# SPDT_FET_SW_driver.net
KiCad netlist of a schematic drawn in Altium Designer
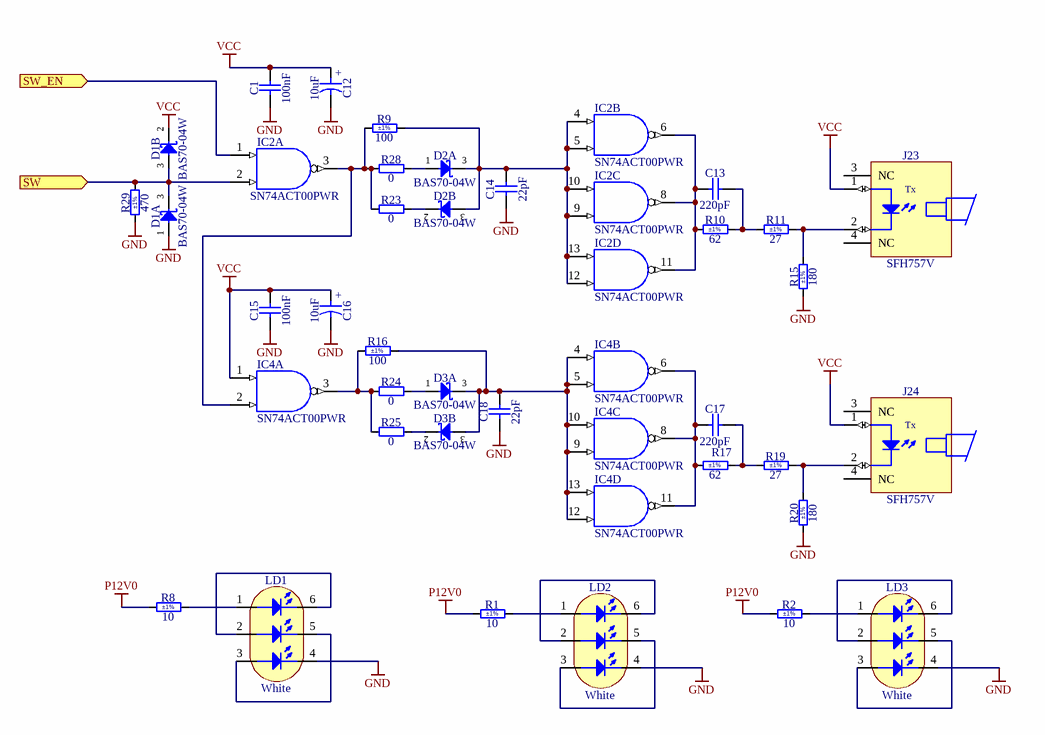
[diagram p0: SPDT_FET_SW_driver.SchDoc]

(export (version "E")
  (design (tool "Eeschema 10.0.6"))
  (components
    (comp (ref "C1")
      (value "100nF")
      (footprint "CAPC1005X55N")
      (description "Non-polarised capacitor")
      (fields
        (field (name "PART NUMBER") "CC0402_100NF_16V_10%_X7R")
        (field (name "VOLTAGE") "16V")
        (field (name "AUTHOR") "CERN DEM JLC")
      )
      (libsource (lib "Capacitors") (part "Capacitor - non polarized"))
    )
    (comp (ref "C12")
      (value "10uF")
      (footprint "CAPMP3216X180N")
      (description "Polarised capacitor")
      (fields
        (field (name "PART NUMBER") "CTE3216-18_10UF_16V_20%_AVX_TCJ")
        (field (name "VOLTAGE") "16V")
        (field (name "AUTHOR") "CERN DEM JLC")
      )
      (libsource (lib "Capacitors") (part "Capacitor - polarized"))
    )
    (comp (ref "C13")
      (value "220pF")
      (footprint "CAPC1608X87N")
      (description "Non-polarised capacitor")
      (fields
        (field (name "PART NUMBER") "CC0603_220PF_50V_5%_NP0")
        (field (name "VOLTAGE") "50V")
        (field (name "AUTHOR") "CERN DEM JLC")
      )
      (libsource (lib "Capacitors") (part "Capacitor - non polarized"))
    )
    (comp (ref "C14")
      (value "22pF")
      (footprint "CAPC1608X87N")
      (description "Non-polarised capacitor")
      (fields
        (field (name "PART NUMBER") "CC0603_22PF_50V_5%_NP0")
        (field (name "VOLTAGE") "50V")
        (field (name "AUTHOR") "CERN DEM JLC")
      )
      (libsource (lib "Capacitors") (part "Capacitor - non polarized"))
    )
    (comp (ref "C15")
      (value "100nF")
      (footprint "CAPC1005X55N")
      (description "Non-polarised capacitor")
      (fields
        (field (name "PART NUMBER") "CC0402_100NF_16V_10%_X7R")
        (field (name "VOLTAGE") "16V")
        (field (name "AUTHOR") "CERN DEM JLC")
      )
      (libsource (lib "Capacitors") (part "Capacitor - non polarized"))
    )
    (comp (ref "C16")
      (value "10uF")
      (footprint "CAPMP3216X180N")
      (description "Polarised capacitor")
      (fields
        (field (name "PART NUMBER") "CTE3216-18_10UF_16V_20%_AVX_TCJ")
        (field (name "VOLTAGE") "16V")
        (field (name "AUTHOR") "CERN DEM JLC")
      )
      (libsource (lib "Capacitors") (part "Capacitor - polarized"))
    )
    (comp (ref "C17")
      (value "220pF")
      (footprint "CAPC1608X87N")
      (description "Non-polarised capacitor")
      (fields
        (field (name "PART NUMBER") "CC0603_220PF_50V_5%_NP0")
        (field (name "VOLTAGE") "50V")
        (field (name "AUTHOR") "CERN DEM JLC")
      )
      (libsource (lib "Capacitors") (part "Capacitor - non polarized"))
    )
    (comp (ref "C18")
      (value "22pF")
      (footprint "CAPC1608X87N")
      (description "Non-polarised capacitor")
      (fields
        (field (name "PART NUMBER") "CC0603_22PF_50V_5%_NP0")
        (field (name "VOLTAGE") "50V")
        (field (name "AUTHOR") "CERN DEM JLC")
      )
      (libsource (lib "Capacitors") (part "Capacitor - non polarized"))
    )
    (comp (ref "D1")
      (value "BAS70-04W")
      (footprint "SOT65P210X110-3N")
      (description "Serial Schottky Diode")
      (fields
        (field (name "VOLTAGE") "70V")
        (field (name "POWER") "70mA")
        (field (name "AUTHOR") "CERN DEM JLC")
      )
      (libsource (lib "ICs And Semiconductors") (part "Diode Schottky x2 A1C3_A3C2"))
    )
    (comp (ref "D2")
      (value "BAS70-04W")
      (footprint "SOT65P210X110-3N")
      (description "Serial Schottky Diode")
      (fields
        (field (name "VOLTAGE") "70V")
        (field (name "POWER") "70mA")
        (field (name "AUTHOR") "CERN DEM JLC")
      )
      (libsource (lib "ICs And Semiconductors") (part "Diode Schottky x2 A1C3_A3C2"))
    )
    (comp (ref "D3")
      (value "BAS70-04W")
      (footprint "SOT65P210X110-3N")
      (description "Serial Schottky Diode")
      (fields
        (field (name "VOLTAGE") "70V")
        (field (name "POWER") "70mA")
        (field (name "AUTHOR") "CERN DEM JLC")
      )
      (libsource (lib "ICs And Semiconductors") (part "Diode Schottky x2 A1C3_A3C2"))
    )
    (comp (ref "IC2")
      (value "SN74ACT00PWR")
      (footprint "SOP65P640X120-14N")
      (description "Quad 2-Input NAND Gate")
      (fields (field (name "MANUFACTURER") "TEXAS INSTRUMENTS") (field (name "AUTHOR") "CERN DEM JLC"))
      (libsource (lib "ICs And Semiconductors") (part "7400"))
    )
    (comp (ref "IC4")
      (value "SN74ACT00PWR")
      (footprint "SOP65P640X120-14N")
      (description "Quad 2-Input NAND Gate")
      (fields (field (name "MANUFACTURER") "TEXAS INSTRUMENTS") (field (name "AUTHOR") "CERN DEM JLC"))
      (libsource (lib "ICs And Semiconductors") (part "7400"))
    )
    (comp (ref "J23")
      (value "SFH757V")
      (footprint "SFH756V")
      (description "Plastic Connector Housing For Plastic Fiber Optic Photodiode Detector")
      (fields
        (field (name "MANUFACTURER") "AVAGO TECHNOLOGIES")
        (field (name "MANUFACTURER PART NUMBER") "SFH756V or SP000063814")
        (field (name "AUTHOR") "CERN DEM JLC")
      )
      (libsource (lib "Connectors") (part "SFH756V"))
    )
    (comp (ref "J24")
      (value "SFH757V")
      (footprint "SFH756V")
      (description "Plastic Connector Housing For Plastic Fiber Optic Photodiode Detector")
      (fields
        (field (name "MANUFACTURER") "AVAGO TECHNOLOGIES")
        (field (name "MANUFACTURER PART NUMBER") "SFH756V or SP000063814")
        (field (name "AUTHOR") "CERN DEM JLC")
      )
      (libsource (lib "Connectors") (part "SFH756V"))
    )
    (comp (ref "LD1")
      (value "White")
      (footprint "LED_CREE_CLP6B-WKW")
      (description "PLCC6 3 in 1 Surface Mount, Cool White LED")
      (fields
        (field (name "PART NUMBER") "LED_CREE_CLP6B-WKW-CD0E0233")
        (field (name "MANUFACTURER") "CREE")
        (field (name "AUTHOR") "CERN DEM JMW")
      )
      (libsource (lib "ICs And Semiconductors") (part "LED_CREE_CLP6B-WKW"))
    )
    (comp (ref "LD2")
      (value "White")
      (footprint "LED_CREE_CLP6B-WKW")
      (description "PLCC6 3 in 1 Surface Mount, Cool White LED")
      (fields
        (field (name "PART NUMBER") "LED_CREE_CLP6B-WKW-CD0E0233")
        (field (name "MANUFACTURER") "CREE")
        (field (name "AUTHOR") "CERN DEM JMW")
      )
      (libsource (lib "ICs And Semiconductors") (part "LED_CREE_CLP6B-WKW"))
    )
    (comp (ref "LD3")
      (value "White")
      (footprint "LED_CREE_CLP6B-WKW")
      (description "PLCC6 3 in 1 Surface Mount, Cool White LED")
      (fields
        (field (name "PART NUMBER") "LED_CREE_CLP6B-WKW-CD0E0233")
        (field (name "MANUFACTURER") "CREE")
        (field (name "AUTHOR") "CERN DEM JMW")
      )
      (libsource (lib "ICs And Semiconductors") (part "LED_CREE_CLP6B-WKW"))
    )
    (comp (ref "R1")
      (value "10")
      (footprint "RESC3216X65N")
      (description "Resistor - 1%")
      (fields
        (field (name "TOLERANCE") "±1%")
        (field (name "PART NUMBER") "R1206_10R_1%_0.25W_100PPM")
        (field (name "POWER") "0.25W")
        (field (name "AUTHOR") "CERN DEM BC")
      )
      (libsource (lib "Resistors") (part "Resistor - 1%"))
    )
    (comp (ref "R2")
      (value "10")
      (footprint "RESC3216X65N")
      (description "Resistor - 1%")
      (fields
        (field (name "TOLERANCE") "±1%")
        (field (name "PART NUMBER") "R1206_10R_1%_0.25W_100PPM")
        (field (name "POWER") "0.25W")
        (field (name "AUTHOR") "CERN DEM BC")
      )
      (libsource (lib "Resistors") (part "Resistor - 1%"))
    )
    (comp (ref "R8")
      (value "10")
      (footprint "RESC3216X65N")
      (description "Resistor - 1%")
      (fields
        (field (name "TOLERANCE") "±1%")
        (field (name "PART NUMBER") "R1206_10R_1%_0.25W_100PPM")
        (field (name "POWER") "0.25W")
        (field (name "AUTHOR") "CERN DEM BC")
      )
      (libsource (lib "Resistors") (part "Resistor - 1%"))
    )
    (comp (ref "R9")
      (value "100")
      (footprint "RESC1608X55N")
      (description "Resistor - 1%")
      (fields
        (field (name "TOLERANCE") "±1%")
        (field (name "PART NUMBER") "R0603_100R_1%_0.1W_100PPM")
        (field (name "POWER") "0.1W")
        (field (name "AUTHOR") "CERN DEM JLC")
      )
      (libsource (lib "Resistors") (part "Resistor - 1%"))
    )
    (comp (ref "R10")
      (value "62")
      (footprint "RESC2012X60N")
      (description "Resistor - 1%")
      (fields
        (field (name "TOLERANCE") "±1%")
        (field (name "PART NUMBER") "R0805_62R_1%_0.125W_100PPM")
        (field (name "POWER") "0.125W")
        (field (name "AUTHOR") "CERN DEM JLC")
      )
      (libsource (lib "Resistors") (part "Resistor - 1%"))
    )
    (comp (ref "R11")
      (value "27")
      (footprint "RESC2012X60N")
      (description "Resistor - 1%")
      (fields
        (field (name "TOLERANCE") "±1%")
        (field (name "PART NUMBER") "R0805_27R_1%_0.125W_100PPM")
        (field (name "POWER") "0.125W")
        (field (name "AUTHOR") "CERN DEM JLC")
      )
      (libsource (lib "Resistors") (part "Resistor - 1%"))
    )
    (comp (ref "R15")
      (value "180")
      (footprint "RESC3216X65N")
      (description "Resistor - 1%")
      (fields
        (field (name "TOLERANCE") "±1%")
        (field (name "PART NUMBER") "R1206_180R_1%_0.25W_100PPM")
        (field (name "POWER") "0.25W")
        (field (name "AUTHOR") "CERN DEM JLC")
      )
      (libsource (lib "Resistors") (part "Resistor - 1%"))
    )
    (comp (ref "R16")
      (value "100")
      (footprint "RESC1608X55N")
      (description "Resistor - 1%")
      (fields
        (field (name "TOLERANCE") "±1%")
        (field (name "PART NUMBER") "R0603_100R_1%_0.1W_100PPM")
        (field (name "POWER") "0.1W")
        (field (name "AUTHOR") "CERN DEM JLC")
      )
      (libsource (lib "Resistors") (part "Resistor - 1%"))
    )
    (comp (ref "R17")
      (value "62")
      (footprint "RESC2012X60N")
      (description "Resistor - 1%")
      (fields
        (field (name "TOLERANCE") "±1%")
        (field (name "PART NUMBER") "R0805_62R_1%_0.125W_100PPM")
        (field (name "POWER") "0.125W")
        (field (name "AUTHOR") "CERN DEM JLC")
      )
      (libsource (lib "Resistors") (part "Resistor - 1%"))
    )
    (comp (ref "R19")
      (value "27")
      (footprint "RESC2012X60N")
      (description "Resistor - 1%")
      (fields
        (field (name "TOLERANCE") "±1%")
        (field (name "PART NUMBER") "R0805_27R_1%_0.125W_100PPM")
        (field (name "POWER") "0.125W")
        (field (name "AUTHOR") "CERN DEM JLC")
      )
      (libsource (lib "Resistors") (part "Resistor - 1%"))
    )
    (comp (ref "R20")
      (value "180")
      (footprint "RESC3216X65N")
      (description "Resistor - 1%")
      (fields
        (field (name "TOLERANCE") "±1%")
        (field (name "PART NUMBER") "R1206_180R_1%_0.25W_100PPM")
        (field (name "POWER") "0.25W")
        (field (name "AUTHOR") "CERN DEM JLC")
      )
      (libsource (lib "Resistors") (part "Resistor - 1%"))
    )
    (comp (ref "R23")
      (value "0")
      (footprint "RESC1608X55N")
      (description "Resistor")
      (fields
        (field (name "PART NUMBER") "R0603_0R_JUMPER")
        (field (name "MANUFACTURER") "GENERIC")
        (field (name "AUTHOR") "CERN DEM JLC")
      )
      (libsource (lib "Resistors") (part "Resistor"))
    )
    (comp (ref "R24")
      (value "0")
      (footprint "RESC1608X55N")
      (description "Resistor")
      (fields
        (field (name "PART NUMBER") "R0603_0R_JUMPER")
        (field (name "MANUFACTURER") "GENERIC")
        (field (name "AUTHOR") "CERN DEM JLC")
      )
      (libsource (lib "Resistors") (part "Resistor"))
    )
    (comp (ref "R25")
      (value "0")
      (footprint "RESC1608X55N")
      (description "Resistor")
      (fields
        (field (name "PART NUMBER") "R0603_0R_JUMPER")
        (field (name "MANUFACTURER") "GENERIC")
        (field (name "AUTHOR") "CERN DEM JLC")
      )
      (libsource (lib "Resistors") (part "Resistor"))
    )
    (comp (ref "R28")
      (value "0")
      (footprint "RESC1608X55N")
      (description "Resistor")
      (fields
        (field (name "PART NUMBER") "R0603_0R_JUMPER")
        (field (name "MANUFACTURER") "GENERIC")
        (field (name "AUTHOR") "CERN DEM JLC")
      )
      (libsource (lib "Resistors") (part "Resistor"))
    )
    (comp (ref "R29")
      (value "470")
      (footprint "RESC1608X55N")
      (description "Resistor - 1%")
      (fields
        (field (name "TOLERANCE") "±1%")
        (field (name "PART NUMBER") "R0603_470R_1%_0.1W_100PPM")
        (field (name "POWER") "0.1W")
        (field (name "AUTHOR") "CERN DEM JLC")
      )
      (libsource (lib "Resistors") (part "Resistor - 1%"))
    )
  )
  (nets
    (net (code "1") (name "/SW") (class "Default")
      (node (ref "D1") (pin "3") (pinfunction "COMAC_3") (pintype "passive"))
      (node (ref "IC2") (pin "2") (pinfunction "B_2") (pintype "input"))
      (node (ref "R29") (pin "2") (pinfunction "2_2") (pintype "passive"))
    )
    (net (code "2") (name "/SW_EN") (class "Default")
      (node (ref "IC2") (pin "1") (pinfunction "A_1") (pintype "input"))
    )
    (net (code "3") (name "GND") (class "Default")
      (node (ref "C1") (pin "1") (pinfunction "1_1") (pintype "passive"))
      (node (ref "C12") (pin "2") (pinfunction "2_2") (pintype "passive"))
      (node (ref "C14") (pin "1") (pinfunction "1_1") (pintype "passive"))
      (node (ref "C15") (pin "1") (pinfunction "1_1") (pintype "passive"))
      (node (ref "C16") (pin "2") (pinfunction "2_2") (pintype "passive"))
      (node (ref "C18") (pin "1") (pinfunction "1_1") (pintype "passive"))
      (node (ref "D1") (pin "1") (pinfunction "A_1") (pintype "passive"))
      (node (ref "IC2") (pin "7") (pinfunction "GND_7") (pintype "power_in"))
      (node (ref "IC4") (pin "7") (pinfunction "GND_7") (pintype "power_in"))
      (node (ref "LD1") (pin "4") (pinfunction "C3_4") (pintype "passive"))
      (node (ref "LD2") (pin "4") (pinfunction "C3_4") (pintype "passive"))
      (node (ref "LD3") (pin "4") (pinfunction "C3_4") (pintype "passive"))
      (node (ref "R15") (pin "1") (pinfunction "1_1") (pintype "passive"))
      (node (ref "R20") (pin "1") (pinfunction "1_1") (pintype "passive"))
      (node (ref "R29") (pin "1") (pinfunction "1_1") (pintype "passive"))
    )
    (net (code "4") (name "Net-(C13-Pad2)") (class "Default")
      (node (ref "C13") (pin "2") (pinfunction "2_2") (pintype "passive"))
      (node (ref "R10") (pin "2") (pinfunction "2_2") (pintype "passive"))
      (node (ref "R11") (pin "1") (pinfunction "1_1") (pintype "passive"))
    )
    (net (code "5") (name "Net-(C17-Pad2)") (class "Default")
      (node (ref "C17") (pin "2") (pinfunction "2_2") (pintype "passive"))
      (node (ref "R17") (pin "2") (pinfunction "2_2") (pintype "passive"))
      (node (ref "R19") (pin "1") (pinfunction "1_1") (pintype "passive"))
    )
    (net (code "6") (name "Net-(D2A-A)") (class "Default")
      (node (ref "D2") (pin "1") (pinfunction "A_1") (pintype "passive"))
      (node (ref "R28") (pin "2") (pinfunction "2_2") (pintype "passive"))
    )
    (net (code "7") (name "Net-(D2A-COMAC)") (class "Default")
      (node (ref "C14") (pin "2") (pinfunction "2_2") (pintype "passive"))
      (node (ref "D2") (pin "3") (pinfunction "COMAC_3") (pintype "passive"))
      (node (ref "IC2") (pin "10") (pinfunction "A_10") (pintype "input"))
      (node (ref "IC2") (pin "12") (pinfunction "B_12") (pintype "input"))
      (node (ref "IC2") (pin "13") (pinfunction "A_13") (pintype "input"))
      (node (ref "IC2") (pin "4") (pinfunction "A_4") (pintype "input"))
      (node (ref "IC2") (pin "5") (pinfunction "B_5") (pintype "input"))
      (node (ref "IC2") (pin "9") (pinfunction "B_9") (pintype "input"))
      (node (ref "R9") (pin "2") (pinfunction "2_2") (pintype "passive"))
    )
    (net (code "8") (name "Net-(D2B-C)") (class "Default")
      (node (ref "D2") (pin "2") (pinfunction "C_2") (pintype "passive"))
      (node (ref "R23") (pin "2") (pinfunction "2_2") (pintype "passive"))
    )
    (net (code "9") (name "Net-(D3A-A)") (class "Default")
      (node (ref "D3") (pin "1") (pinfunction "A_1") (pintype "passive"))
      (node (ref "R24") (pin "2") (pinfunction "2_2") (pintype "passive"))
    )
    (net (code "10") (name "Net-(D3A-COMAC)") (class "Default")
      (node (ref "C18") (pin "2") (pinfunction "2_2") (pintype "passive"))
      (node (ref "D3") (pin "3") (pinfunction "COMAC_3") (pintype "passive"))
      (node (ref "IC4") (pin "10") (pinfunction "A_10") (pintype "input"))
      (node (ref "IC4") (pin "12") (pinfunction "B_12") (pintype "input"))
      (node (ref "IC4") (pin "13") (pinfunction "A_13") (pintype "input"))
      (node (ref "IC4") (pin "4") (pinfunction "A_4") (pintype "input"))
      (node (ref "IC4") (pin "5") (pinfunction "B_5") (pintype "input"))
      (node (ref "IC4") (pin "9") (pinfunction "B_9") (pintype "input"))
      (node (ref "R16") (pin "2") (pinfunction "2_2") (pintype "passive"))
    )
    (net (code "11") (name "Net-(D3B-C)") (class "Default")
      (node (ref "D3") (pin "2") (pinfunction "C_2") (pintype "passive"))
      (node (ref "R25") (pin "2") (pinfunction "2_2") (pintype "passive"))
    )
    (net (code "12") (name "Net-(IC2A-~{O})") (class "Default")
      (node (ref "IC2") (pin "3") (pinfunction "~{O}_3") (pintype "output"))
      (node (ref "IC4") (pin "2") (pinfunction "B_2") (pintype "input"))
      (node (ref "R23") (pin "1") (pinfunction "1_1") (pintype "passive"))
      (node (ref "R28") (pin "1") (pinfunction "1_1") (pintype "passive"))
      (node (ref "R9") (pin "1") (pinfunction "1_1") (pintype "passive"))
    )
    (net (code "13") (name "Net-(IC2B-~{O})") (class "Default")
      (node (ref "C13") (pin "1") (pinfunction "1_1") (pintype "passive"))
      (node (ref "IC2") (pin "11") (pinfunction "~{O}_11") (pintype "output"))
      (node (ref "IC2") (pin "6") (pinfunction "~{O}_6") (pintype "output"))
      (node (ref "IC2") (pin "8") (pinfunction "~{O}_8") (pintype "output"))
      (node (ref "R10") (pin "1") (pinfunction "1_1") (pintype "passive"))
    )
    (net (code "14") (name "Net-(IC4A-~{O})") (class "Default")
      (node (ref "IC4") (pin "3") (pinfunction "~{O}_3") (pintype "output"))
      (node (ref "R16") (pin "1") (pinfunction "1_1") (pintype "passive"))
      (node (ref "R24") (pin "1") (pinfunction "1_1") (pintype "passive"))
      (node (ref "R25") (pin "1") (pinfunction "1_1") (pintype "passive"))
    )
    (net (code "15") (name "Net-(IC4B-~{O})") (class "Default")
      (node (ref "C17") (pin "1") (pinfunction "1_1") (pintype "passive"))
      (node (ref "IC4") (pin "11") (pinfunction "~{O}_11") (pintype "output"))
      (node (ref "IC4") (pin "6") (pinfunction "~{O}_6") (pintype "output"))
      (node (ref "IC4") (pin "8") (pinfunction "~{O}_8") (pintype "output"))
      (node (ref "R17") (pin "1") (pinfunction "1_1") (pintype "passive"))
    )
    (net (code "16") (name "Net-(J23-C)") (class "Default")
      (node (ref "J23") (pin "2") (pinfunction "C_2") (pintype "bidirectional"))
      (node (ref "R11") (pin "2") (pinfunction "2_2") (pintype "passive"))
      (node (ref "R15") (pin "2") (pinfunction "2_2") (pintype "passive"))
    )
    (net (code "17") (name "Net-(J24-C)") (class "Default")
      (node (ref "J24") (pin "2") (pinfunction "C_2") (pintype "bidirectional"))
      (node (ref "R19") (pin "2") (pinfunction "2_2") (pintype "passive"))
      (node (ref "R20") (pin "2") (pinfunction "2_2") (pintype "passive"))
    )
    (net (code "18") (name "Net-(LD1-A1)") (class "Default")
      (node (ref "LD1") (pin "1") (pinfunction "A1_1") (pintype "passive"))
      (node (ref "R8") (pin "2") (pinfunction "2_2") (pintype "passive"))
    )
    (net (code "19") (name "Net-(LD1-A2)") (class "Default")
      (node (ref "LD1") (pin "2") (pinfunction "A2_2") (pintype "passive"))
      (node (ref "LD1") (pin "6") (pinfunction "C1_6") (pintype "passive"))
    )
    (net (code "20") (name "Net-(LD1-A3)") (class "Default")
      (node (ref "LD1") (pin "3") (pinfunction "A3_3") (pintype "passive"))
      (node (ref "LD1") (pin "5") (pinfunction "C2_5") (pintype "passive"))
    )
    (net (code "21") (name "Net-(LD2-A1)") (class "Default")
      (node (ref "LD2") (pin "1") (pinfunction "A1_1") (pintype "passive"))
      (node (ref "R1") (pin "2") (pinfunction "2_2") (pintype "passive"))
    )
    (net (code "22") (name "Net-(LD2-A2)") (class "Default")
      (node (ref "LD2") (pin "2") (pinfunction "A2_2") (pintype "passive"))
      (node (ref "LD2") (pin "6") (pinfunction "C1_6") (pintype "passive"))
    )
    (net (code "23") (name "Net-(LD2-A3)") (class "Default")
      (node (ref "LD2") (pin "3") (pinfunction "A3_3") (pintype "passive"))
      (node (ref "LD2") (pin "5") (pinfunction "C2_5") (pintype "passive"))
    )
    (net (code "24") (name "Net-(LD3-A1)") (class "Default")
      (node (ref "LD3") (pin "1") (pinfunction "A1_1") (pintype "passive"))
      (node (ref "R2") (pin "2") (pinfunction "2_2") (pintype "passive"))
    )
    (net (code "25") (name "Net-(LD3-A2)") (class "Default")
      (node (ref "LD3") (pin "2") (pinfunction "A2_2") (pintype "passive"))
      (node (ref "LD3") (pin "6") (pinfunction "C1_6") (pintype "passive"))
    )
    (net (code "26") (name "Net-(LD3-A3)") (class "Default")
      (node (ref "LD3") (pin "3") (pinfunction "A3_3") (pintype "passive"))
      (node (ref "LD3") (pin "5") (pinfunction "C2_5") (pintype "passive"))
    )
    (net (code "27") (name "P12V0") (class "Default")
      (node (ref "R1") (pin "1") (pinfunction "1_1") (pintype "passive"))
      (node (ref "R2") (pin "1") (pinfunction "1_1") (pintype "passive"))
      (node (ref "R8") (pin "1") (pinfunction "1_1") (pintype "passive"))
    )
    (net (code "28") (name "VCC") (class "Default")
      (node (ref "C1") (pin "2") (pinfunction "2_2") (pintype "passive"))
      (node (ref "C12") (pin "1") (pinfunction "1_1") (pintype "passive"))
      (node (ref "C15") (pin "2") (pinfunction "2_2") (pintype "passive"))
      (node (ref "C16") (pin "1") (pinfunction "1_1") (pintype "passive"))
      (node (ref "D1") (pin "2") (pinfunction "C_2") (pintype "passive"))
      (node (ref "IC2") (pin "14") (pinfunction "VCC_14") (pintype "power_in"))
      (node (ref "IC4") (pin "1") (pinfunction "A_1") (pintype "input"))
      (node (ref "IC4") (pin "14") (pinfunction "VCC_14") (pintype "power_in"))
      (node (ref "J23") (pin "1") (pinfunction "A_1") (pintype "bidirectional"))
      (node (ref "J24") (pin "1") (pinfunction "A_1") (pintype "bidirectional"))
    )
    (net (code "29") (name "unconnected-(J23-NC-Pad3)") (class "Default")
      (node (ref "J23") (pin "3") (pinfunction "NC_3") (pintype "passive"))
    )
    (net (code "30") (name "unconnected-(J23-NC-Pad4)") (class "Default")
      (node (ref "J23") (pin "4") (pinfunction "NC_4") (pintype "passive"))
    )
    (net (code "31") (name "unconnected-(J24-NC-Pad3)") (class "Default")
      (node (ref "J24") (pin "3") (pinfunction "NC_3") (pintype "passive"))
    )
    (net (code "32") (name "unconnected-(J24-NC-Pad4)") (class "Default")
      (node (ref "J24") (pin "4") (pinfunction "NC_4") (pintype "passive"))
    )
  )
)
